# Pg4-Power_supply_1.net
KiCad netlist of a schematic drawn in Altium Designer
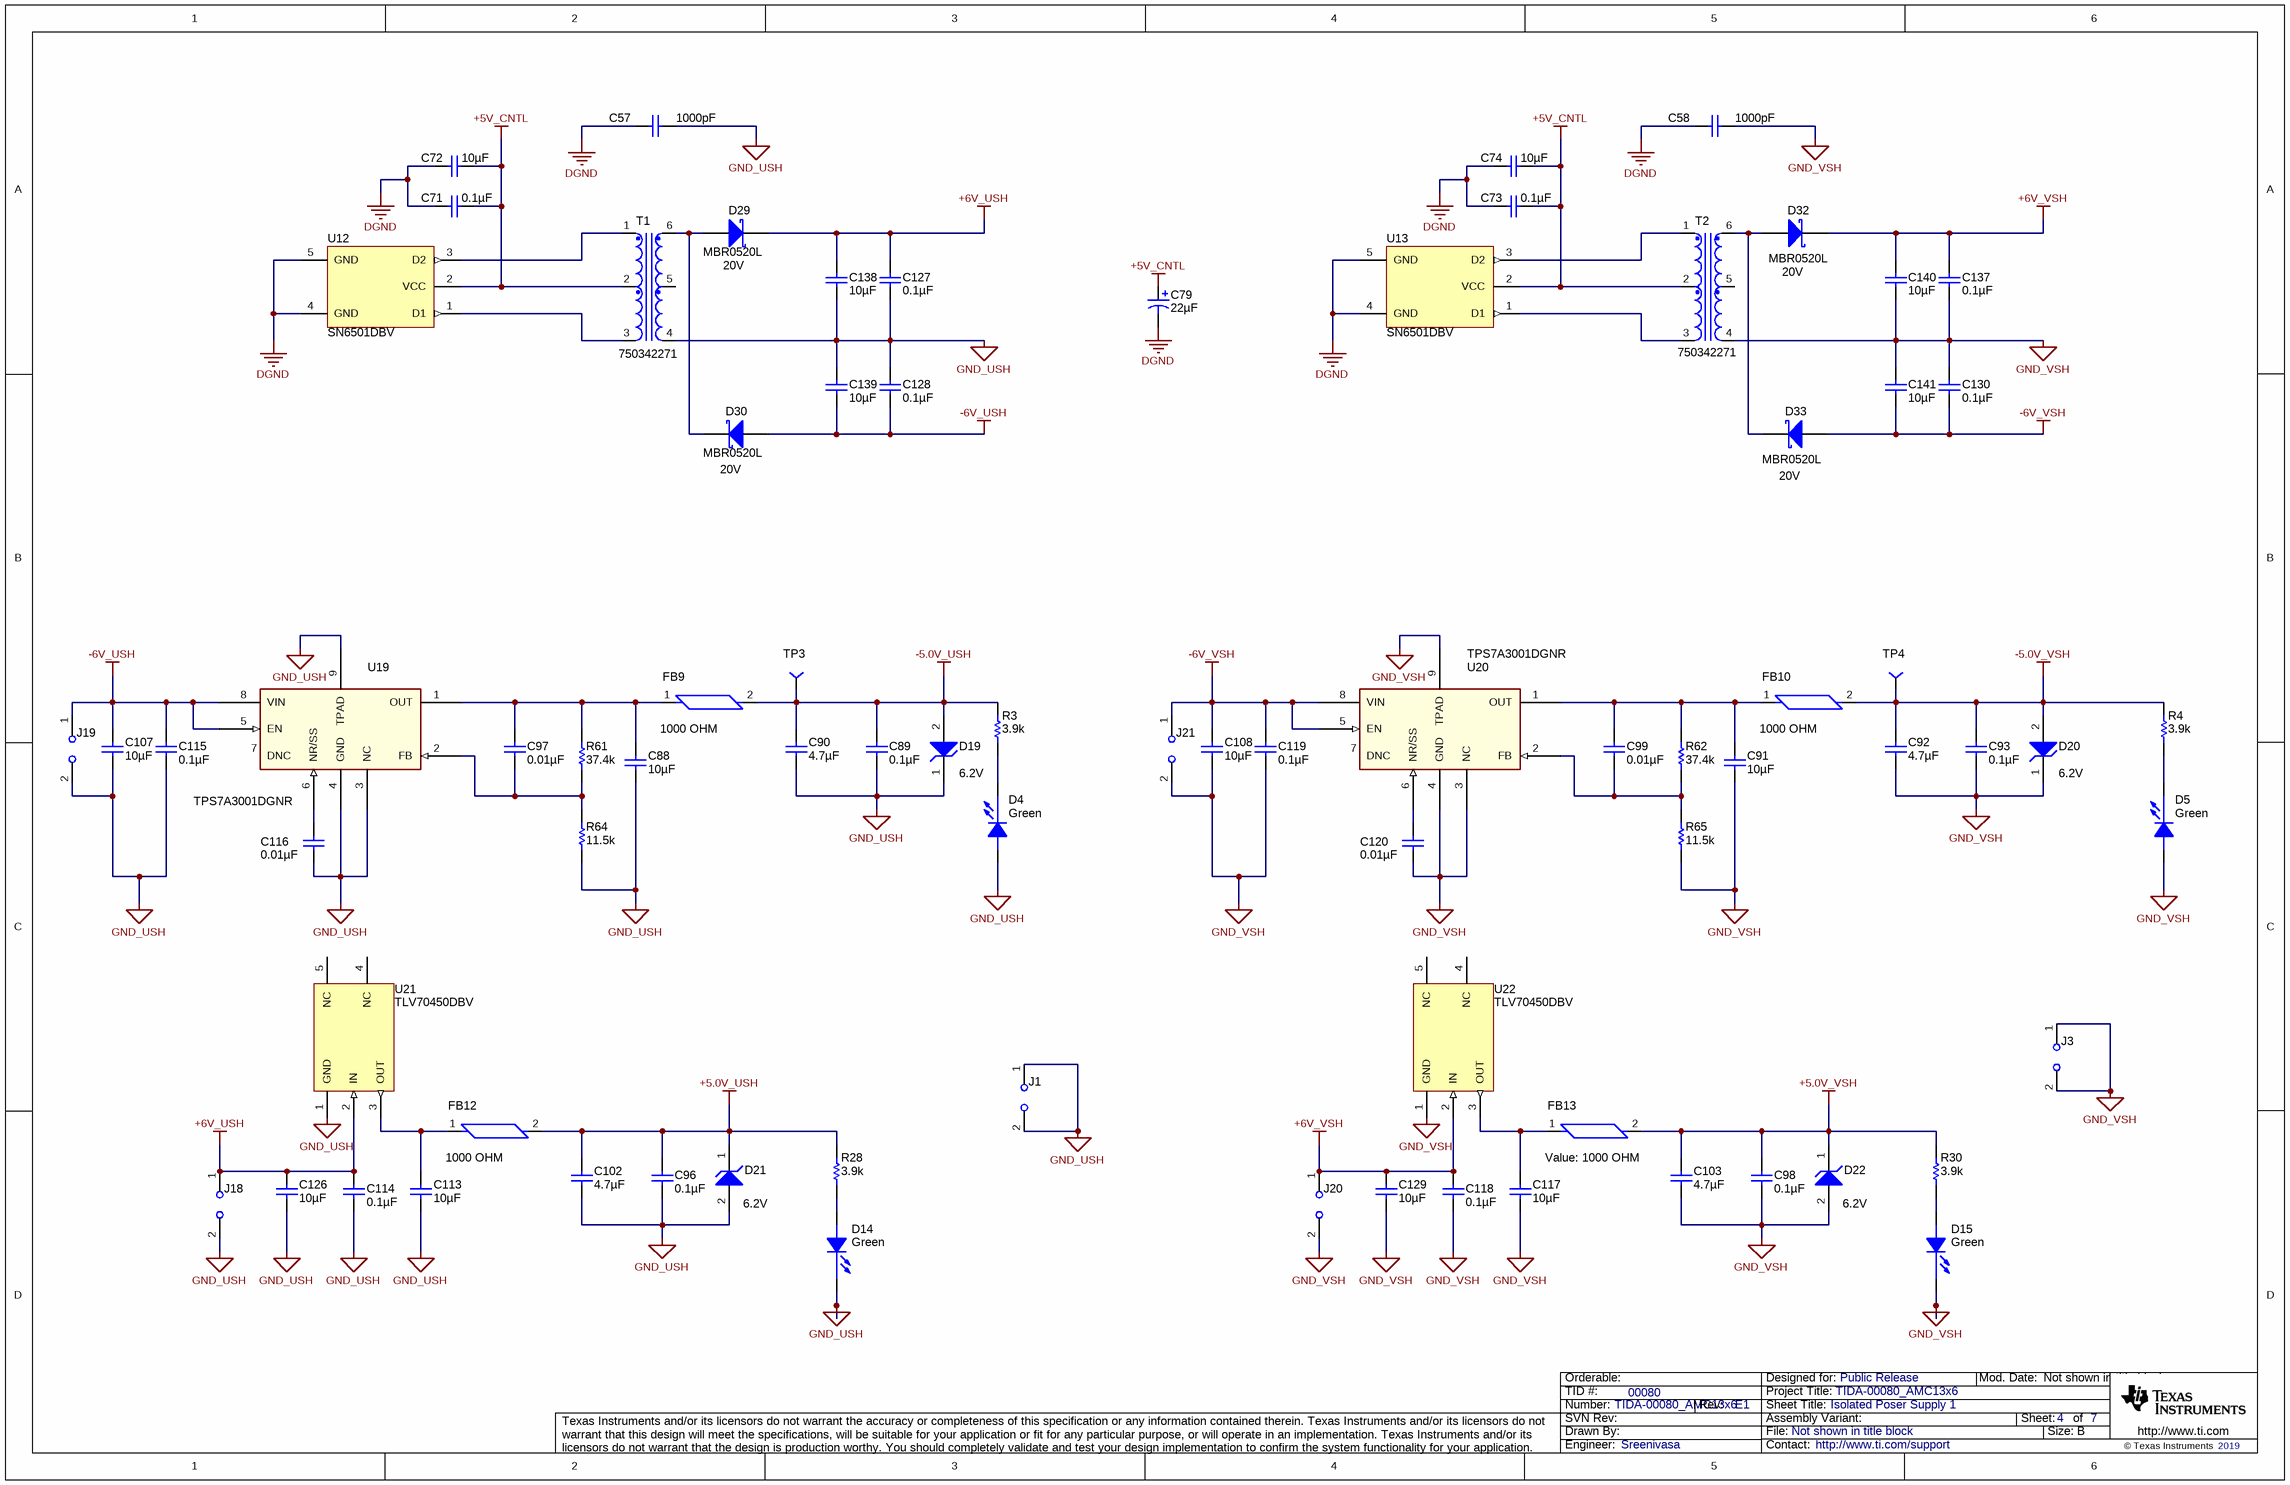
[diagram p0: Pg4-Power supply 1.SchDoc]

(export (version "E")
  (design (tool "Eeschema 10.0.6"))
  (components
    (comp (ref "C57")
      (value "1000pF")
      (footprint "CAP_200mil")
      (description "CAP CER 1000PF 1KV 10% RADIAL")
      (fields
        (field (name "PARTNUMBER") "S102K29Y5PN63J5R")
        (field (name "MANUFACTURER") "Vishay BC Components")
        (field (name "PUBLISHER") "Texas Instruments")
      )
      (libsource (lib "TI-INDIA-ALTIUM") (part "202R18W102KV4E"))
    )
    (comp (ref "C58")
      (value "1000pF")
      (footprint "CAP_200mil")
      (description "CAP CER 1000PF 1KV 10% RADIAL")
      (fields
        (field (name "PARTNUMBER") "S102K29Y5PN63J5R")
        (field (name "MANUFACTURER") "Vishay BC Components")
        (field (name "PUBLISHER") "Texas Instruments")
      )
      (libsource (lib "TI-INDIA-ALTIUM") (part "202R18W102KV4E"))
    )
    (comp (ref "C71")
      (value "~")
      (footprint "ISE_MCS_SDM_E1_20MAY:0603")
      (description "CAP, CERM, 0.1uF, 50V, +/-10%, X7R, 0603")
      (fields
        (field (name "PARTNUMBER") "C0603C104K5RACTU")
        (field (name "VALUEDISPLAYED") "0.1µF")
        (field (name "MANUFACTURER") "Kemet")
        (field (name "PUBLISHER") "Texas Instruments")
      )
      (libsource (lib "Capacitor_Ceramic") (part "C0603C104K5RACTU"))
    )
    (comp (ref "C72")
      (value "~")
      (footprint "ISE_MCS_SDM_E1_20MAY:1210")
      (description "CAP, CERM, 10uF, 35V, +/-20%, X7R, 1210")
      (fields
        (field (name "PARTNUMBER") "GMK325AB7106MM-T")
        (field (name "VALUEDISPLAYED") "10µF")
        (field (name "MANUFACTURER") "Taiyo Yuden")
        (field (name "PUBLISHER") "Texas Instruments")
      )
      (libsource (lib "Capacitor_Ceramic") (part "GMK325AB7106MM-T"))
    )
    (comp (ref "C73")
      (value "~")
      (footprint "ISE_MCS_SDM_E1_20MAY:0603")
      (description "CAP, CERM, 0.1uF, 50V, +/-10%, X7R, 0603")
      (fields
        (field (name "PARTNUMBER") "C0603C104K5RACTU")
        (field (name "VALUEDISPLAYED") "0.1µF")
        (field (name "MANUFACTURER") "Kemet")
        (field (name "PUBLISHER") "Texas Instruments")
      )
      (libsource (lib "Capacitor_Ceramic") (part "C0603C104K5RACTU"))
    )
    (comp (ref "C74")
      (value "~")
      (footprint "ISE_MCS_SDM_E1_20MAY:1210")
      (description "CAP, CERM, 10uF, 35V, +/-20%, X7R, 1210")
      (fields
        (field (name "PARTNUMBER") "GMK325AB7106MM-T")
        (field (name "VALUEDISPLAYED") "10µF")
        (field (name "MANUFACTURER") "Taiyo Yuden")
        (field (name "PUBLISHER") "Texas Instruments")
      )
      (libsource (lib "Capacitor_Ceramic") (part "GMK325AB7106MM-T"))
    )
    (comp (ref "C79")
      (value "UUD1E220MCL1GS")
      (footprint "ISE_MCS_SDM_E1_20MAY:SM_RADIAL_5MM")
      (description "CAP, AL, 22uF, 25V, +/-20%, 0.76 ohm, SMD")
      (fields
        (field (name "VALUEDISPLAYED") "22µF")
        (field (name "MANUFACTURER") "Nichicon")
        (field (name "PUBLISHER") "Texas Instruments")
      )
      (libsource (lib "Capacitor_Aluminum") (part "UUD1E220MCL1GS"))
    )
    (comp (ref "C88")
      (value "~")
      (footprint "ISE_MCS_SDM_E1_20MAY:1210")
      (description "CAP, CERM, 10uF, 35V, +/-20%, X7R, 1210")
      (fields
        (field (name "PARTNUMBER") "GMK325AB7106MM-T")
        (field (name "VALUEDISPLAYED") "10µF")
        (field (name "MANUFACTURER") "Taiyo Yuden")
        (field (name "PUBLISHER") "Texas Instruments")
      )
      (libsource (lib "Capacitor_Ceramic") (part "GMK325AB7106MM-T"))
    )
    (comp (ref "C89")
      (value "~")
      (footprint "ISE_MCS_SDM_E1_20MAY:0603")
      (description "CAP, CERM, 0.1uF, 50V, +/-10%, X7R, 0603")
      (fields
        (field (name "PARTNUMBER") "C0603C104K5RACTU")
        (field (name "VALUEDISPLAYED") "0.1µF")
        (field (name "MANUFACTURER") "Kemet")
        (field (name "PUBLISHER") "Texas Instruments")
      )
      (libsource (lib "Capacitor_Ceramic") (part "C0603C104K5RACTU"))
    )
    (comp (ref "C90")
      (value "~")
      (footprint "ISE_MCS_SDM_E1_20MAY:0805_HV")
      (description "CAP, CERM, 4.7uF, 50V, +/-10%, X5R, 0805")
      (fields
        (field (name "PARTNUMBER") "C2012X5R1H475K125AB")
        (field (name "VALUEDISPLAYED") "4.7µF")
        (field (name "MANUFACTURER") "TDK")
        (field (name "PUBLISHER") "Texas Instruments")
      )
      (libsource (lib "Capacitor_Ceramic") (part "C2012X5R1H475K125AB"))
    )
    (comp (ref "C91")
      (value "~")
      (footprint "ISE_MCS_SDM_E1_20MAY:1210")
      (description "CAP, CERM, 10uF, 35V, +/-20%, X7R, 1210")
      (fields
        (field (name "PARTNUMBER") "GMK325AB7106MM-T")
        (field (name "VALUEDISPLAYED") "10µF")
        (field (name "MANUFACTURER") "Taiyo Yuden")
        (field (name "PUBLISHER") "Texas Instruments")
      )
      (libsource (lib "Capacitor_Ceramic") (part "GMK325AB7106MM-T"))
    )
    (comp (ref "C92")
      (value "~")
      (footprint "ISE_MCS_SDM_E1_20MAY:0805_HV")
      (description "CAP, CERM, 4.7uF, 50V, +/-10%, X5R, 0805")
      (fields
        (field (name "PARTNUMBER") "C2012X5R1H475K125AB")
        (field (name "VALUEDISPLAYED") "4.7µF")
        (field (name "MANUFACTURER") "TDK")
        (field (name "PUBLISHER") "Texas Instruments")
      )
      (libsource (lib "Capacitor_Ceramic") (part "C2012X5R1H475K125AB"))
    )
    (comp (ref "C93")
      (value "~")
      (footprint "ISE_MCS_SDM_E1_20MAY:0603")
      (description "CAP, CERM, 0.1uF, 50V, +/-10%, X7R, 0603")
      (fields
        (field (name "PARTNUMBER") "C0603C104K5RACTU")
        (field (name "VALUEDISPLAYED") "0.1µF")
        (field (name "MANUFACTURER") "Kemet")
        (field (name "PUBLISHER") "Texas Instruments")
      )
      (libsource (lib "Capacitor_Ceramic") (part "C0603C104K5RACTU"))
    )
    (comp (ref "C96")
      (value "~")
      (footprint "ISE_MCS_SDM_E1_20MAY:0603")
      (description "CAP, CERM, 0.1uF, 50V, +/-10%, X7R, 0603")
      (fields
        (field (name "PARTNUMBER") "C0603C104K5RACTU")
        (field (name "VALUEDISPLAYED") "0.1µF")
        (field (name "MANUFACTURER") "Kemet")
        (field (name "PUBLISHER") "Texas Instruments")
      )
      (libsource (lib "Capacitor_Ceramic") (part "C0603C104K5RACTU"))
    )
    (comp (ref "C97")
      (value "~")
      (footprint "ISE_MCS_SDM_E1_20MAY:0603")
      (description "CAP, CERM, 0.01uF, 100V, +/-5%, X7R, 0603")
      (fields
        (field (name "PARTNUMBER") "06031C103J4Z4A")
        (field (name "VALUEDISPLAYED") "0.01µF")
        (field (name "MANUFACTURER") "AVX")
        (field (name "PUBLISHER") "Texas Instruments")
      )
      (libsource (lib "Capacitor_Ceramic") (part "06031C103JAT2A"))
    )
    (comp (ref "C98")
      (value "~")
      (footprint "ISE_MCS_SDM_E1_20MAY:0603")
      (description "CAP, CERM, 0.1uF, 50V, +/-10%, X7R, 0603")
      (fields
        (field (name "PARTNUMBER") "C0603C104K5RACTU")
        (field (name "VALUEDISPLAYED") "0.1µF")
        (field (name "MANUFACTURER") "Kemet")
        (field (name "PUBLISHER") "Texas Instruments")
      )
      (libsource (lib "Capacitor_Ceramic") (part "C0603C104K5RACTU"))
    )
    (comp (ref "C99")
      (value "~")
      (footprint "ISE_MCS_SDM_E1_20MAY:0603")
      (description "CAP, CERM, 0.01uF, 100V, +/-5%, X7R, 0603")
      (fields
        (field (name "PARTNUMBER") "06031C103J4Z4A")
        (field (name "VALUEDISPLAYED") "0.01µF")
        (field (name "MANUFACTURER") "AVX")
        (field (name "PUBLISHER") "Texas Instruments")
      )
      (libsource (lib "Capacitor_Ceramic") (part "06031C103JAT2A"))
    )
    (comp (ref "C102")
      (value "~")
      (footprint "ISE_MCS_SDM_E1_20MAY:0805_HV")
      (description "CAP, CERM, 4.7uF, 50V, +/-10%, X5R, 0805")
      (fields
        (field (name "PARTNUMBER") "C2012X5R1H475K125AB")
        (field (name "VALUEDISPLAYED") "4.7µF")
        (field (name "MANUFACTURER") "TDK")
        (field (name "PUBLISHER") "Texas Instruments")
      )
      (libsource (lib "Capacitor_Ceramic") (part "C2012X5R1H475K125AB"))
    )
    (comp (ref "C103")
      (value "~")
      (footprint "ISE_MCS_SDM_E1_20MAY:0805_HV")
      (description "CAP, CERM, 4.7uF, 50V, +/-10%, X5R, 0805")
      (fields
        (field (name "PARTNUMBER") "C2012X5R1H475K125AB")
        (field (name "VALUEDISPLAYED") "4.7µF")
        (field (name "MANUFACTURER") "TDK")
        (field (name "PUBLISHER") "Texas Instruments")
      )
      (libsource (lib "Capacitor_Ceramic") (part "C2012X5R1H475K125AB"))
    )
    (comp (ref "C107")
      (value "~")
      (footprint "ISE_MCS_SDM_E1_20MAY:1210")
      (description "CAP, CERM, 10uF, 35V, +/-20%, X7R, 1210")
      (fields
        (field (name "PARTNUMBER") "GMK325AB7106MM-T")
        (field (name "VALUEDISPLAYED") "10µF")
        (field (name "MANUFACTURER") "Taiyo Yuden")
        (field (name "PUBLISHER") "Texas Instruments")
      )
      (libsource (lib "Capacitor_Ceramic") (part "GMK325AB7106MM-T"))
    )
    (comp (ref "C108")
      (value "~")
      (footprint "ISE_MCS_SDM_E1_20MAY:1210")
      (description "CAP, CERM, 10uF, 35V, +/-20%, X7R, 1210")
      (fields
        (field (name "PARTNUMBER") "GMK325AB7106MM-T")
        (field (name "VALUEDISPLAYED") "10µF")
        (field (name "MANUFACTURER") "Taiyo Yuden")
        (field (name "PUBLISHER") "Texas Instruments")
      )
      (libsource (lib "Capacitor_Ceramic") (part "GMK325AB7106MM-T"))
    )
    (comp (ref "C113")
      (value "~")
      (footprint "ISE_MCS_SDM_E1_20MAY:1210")
      (description "CAP, CERM, 10uF, 35V, +/-20%, X7R, 1210")
      (fields
        (field (name "PARTNUMBER") "GMK325AB7106MM-T")
        (field (name "VALUEDISPLAYED") "10µF")
        (field (name "MANUFACTURER") "Taiyo Yuden")
        (field (name "PUBLISHER") "Texas Instruments")
      )
      (libsource (lib "Capacitor_Ceramic") (part "GMK325AB7106MM-T"))
    )
    (comp (ref "C114")
      (value "~")
      (footprint "ISE_MCS_SDM_E1_20MAY:0603")
      (description "CAP, CERM, 0.1uF, 50V, +/-10%, X7R, 0603")
      (fields
        (field (name "PARTNUMBER") "C0603C104K5RACTU")
        (field (name "VALUEDISPLAYED") "0.1µF")
        (field (name "MANUFACTURER") "Kemet")
        (field (name "PUBLISHER") "Texas Instruments")
      )
      (libsource (lib "Capacitor_Ceramic") (part "C0603C104K5RACTU"))
    )
    (comp (ref "C115")
      (value "~")
      (footprint "ISE_MCS_SDM_E1_20MAY:0603")
      (description "CAP, CERM, 0.1uF, 50V, +/-10%, X7R, 0603")
      (fields
        (field (name "PARTNUMBER") "C0603C104K5RACTU")
        (field (name "VALUEDISPLAYED") "0.1µF")
        (field (name "MANUFACTURER") "Kemet")
        (field (name "PUBLISHER") "Texas Instruments")
      )
      (libsource (lib "Capacitor_Ceramic") (part "C0603C104K5RACTU"))
    )
    (comp (ref "C116")
      (value "~")
      (footprint "ISE_MCS_SDM_E1_20MAY:0603")
      (description "CAP, CERM, 0.01uF, 100V, +/-5%, X7R, 0603")
      (fields
        (field (name "PARTNUMBER") "06031C103J4Z4A")
        (field (name "VALUEDISPLAYED") "0.01µF")
        (field (name "MANUFACTURER") "AVX")
        (field (name "PUBLISHER") "Texas Instruments")
      )
      (libsource (lib "Capacitor_Ceramic") (part "06031C103JAT2A"))
    )
    (comp (ref "C117")
      (value "~")
      (footprint "ISE_MCS_SDM_E1_20MAY:1210")
      (description "CAP, CERM, 10uF, 35V, +/-20%, X7R, 1210")
      (fields
        (field (name "PARTNUMBER") "GMK325AB7106MM-T")
        (field (name "VALUEDISPLAYED") "10µF")
        (field (name "MANUFACTURER") "Taiyo Yuden")
        (field (name "PUBLISHER") "Texas Instruments")
      )
      (libsource (lib "Capacitor_Ceramic") (part "GMK325AB7106MM-T"))
    )
    (comp (ref "C118")
      (value "~")
      (footprint "ISE_MCS_SDM_E1_20MAY:0603")
      (description "CAP, CERM, 0.1uF, 50V, +/-10%, X7R, 0603")
      (fields
        (field (name "PARTNUMBER") "C0603C104K5RACTU")
        (field (name "VALUEDISPLAYED") "0.1µF")
        (field (name "MANUFACTURER") "Kemet")
        (field (name "PUBLISHER") "Texas Instruments")
      )
      (libsource (lib "Capacitor_Ceramic") (part "C0603C104K5RACTU"))
    )
    (comp (ref "C119")
      (value "~")
      (footprint "ISE_MCS_SDM_E1_20MAY:0603")
      (description "CAP, CERM, 0.1uF, 50V, +/-10%, X7R, 0603")
      (fields
        (field (name "PARTNUMBER") "C0603C104K5RACTU")
        (field (name "VALUEDISPLAYED") "0.1µF")
        (field (name "MANUFACTURER") "Kemet")
        (field (name "PUBLISHER") "Texas Instruments")
      )
      (libsource (lib "Capacitor_Ceramic") (part "C0603C104K5RACTU"))
    )
    (comp (ref "C120")
      (value "~")
      (footprint "ISE_MCS_SDM_E1_20MAY:0603")
      (description "CAP, CERM, 0.01uF, 100V, +/-5%, X7R, 0603")
      (fields
        (field (name "PARTNUMBER") "06031C103J4Z4A")
        (field (name "VALUEDISPLAYED") "0.01µF")
        (field (name "MANUFACTURER") "AVX")
        (field (name "PUBLISHER") "Texas Instruments")
      )
      (libsource (lib "Capacitor_Ceramic") (part "06031C103JAT2A"))
    )
    (comp (ref "C126")
      (value "~")
      (footprint "ISE_MCS_SDM_E1_20MAY:1210")
      (description "CAP, CERM, 10uF, 35V, +/-20%, X7R, 1210")
      (fields
        (field (name "PARTNUMBER") "GMK325AB7106MM-T")
        (field (name "VALUEDISPLAYED") "10µF")
        (field (name "MANUFACTURER") "Taiyo Yuden")
        (field (name "PUBLISHER") "Texas Instruments")
      )
      (libsource (lib "Capacitor_Ceramic") (part "GMK325AB7106MM-T"))
    )
    (comp (ref "C127")
      (value "~")
      (footprint "ISE_MCS_SDM_E1_20MAY:0603")
      (description "CAP, CERM, 0.1uF, 50V, +/-10%, X7R, 0603")
      (fields
        (field (name "PARTNUMBER") "C0603C104K5RACTU")
        (field (name "VALUEDISPLAYED") "0.1µF")
        (field (name "MANUFACTURER") "Kemet")
        (field (name "PUBLISHER") "Texas Instruments")
      )
      (libsource (lib "Capacitor_Ceramic") (part "C0603C104K5RACTU"))
    )
    (comp (ref "C128")
      (value "~")
      (footprint "ISE_MCS_SDM_E1_20MAY:0603")
      (description "CAP, CERM, 0.1uF, 50V, +/-10%, X7R, 0603")
      (fields
        (field (name "PARTNUMBER") "C0603C104K5RACTU")
        (field (name "VALUEDISPLAYED") "0.1µF")
        (field (name "MANUFACTURER") "Kemet")
        (field (name "PUBLISHER") "Texas Instruments")
      )
      (libsource (lib "Capacitor_Ceramic") (part "C0603C104K5RACTU"))
    )
    (comp (ref "C129")
      (value "~")
      (footprint "ISE_MCS_SDM_E1_20MAY:1210")
      (description "CAP, CERM, 10uF, 35V, +/-20%, X7R, 1210")
      (fields
        (field (name "PARTNUMBER") "GMK325AB7106MM-T")
        (field (name "VALUEDISPLAYED") "10µF")
        (field (name "MANUFACTURER") "Taiyo Yuden")
        (field (name "PUBLISHER") "Texas Instruments")
      )
      (libsource (lib "Capacitor_Ceramic") (part "GMK325AB7106MM-T"))
    )
    (comp (ref "C130")
      (value "~")
      (footprint "ISE_MCS_SDM_E1_20MAY:0603")
      (description "CAP, CERM, 0.1uF, 50V, +/-10%, X7R, 0603")
      (fields
        (field (name "PARTNUMBER") "C0603C104K5RACTU")
        (field (name "VALUEDISPLAYED") "0.1µF")
        (field (name "MANUFACTURER") "Kemet")
        (field (name "PUBLISHER") "Texas Instruments")
      )
      (libsource (lib "Capacitor_Ceramic") (part "C0603C104K5RACTU"))
    )
    (comp (ref "C137")
      (value "~")
      (footprint "ISE_MCS_SDM_E1_20MAY:0603")
      (description "CAP, CERM, 0.1uF, 50V, +/-10%, X7R, 0603")
      (fields
        (field (name "PARTNUMBER") "C0603C104K5RACTU")
        (field (name "VALUEDISPLAYED") "0.1µF")
        (field (name "MANUFACTURER") "Kemet")
        (field (name "PUBLISHER") "Texas Instruments")
      )
      (libsource (lib "Capacitor_Ceramic") (part "C0603C104K5RACTU"))
    )
    (comp (ref "C138")
      (value "~")
      (footprint "ISE_MCS_SDM_E1_20MAY:1210")
      (description "CAP, CERM, 10uF, 35V, +/-20%, X7R, 1210")
      (fields
        (field (name "PARTNUMBER") "GMK325AB7106MM-T")
        (field (name "VALUEDISPLAYED") "10µF")
        (field (name "MANUFACTURER") "Taiyo Yuden")
        (field (name "PUBLISHER") "Texas Instruments")
      )
      (libsource (lib "Capacitor_Ceramic") (part "GMK325AB7106MM-T"))
    )
    (comp (ref "C139")
      (value "~")
      (footprint "ISE_MCS_SDM_E1_20MAY:1210")
      (description "CAP, CERM, 10uF, 35V, +/-20%, X7R, 1210")
      (fields
        (field (name "PARTNUMBER") "GMK325AB7106MM-T")
        (field (name "VALUEDISPLAYED") "10µF")
        (field (name "MANUFACTURER") "Taiyo Yuden")
        (field (name "PUBLISHER") "Texas Instruments")
      )
      (libsource (lib "Capacitor_Ceramic") (part "GMK325AB7106MM-T"))
    )
    (comp (ref "C140")
      (value "~")
      (footprint "ISE_MCS_SDM_E1_20MAY:1210")
      (description "CAP, CERM, 10uF, 35V, +/-20%, X7R, 1210")
      (fields
        (field (name "PARTNUMBER") "GMK325AB7106MM-T")
        (field (name "VALUEDISPLAYED") "10µF")
        (field (name "MANUFACTURER") "Taiyo Yuden")
        (field (name "PUBLISHER") "Texas Instruments")
      )
      (libsource (lib "Capacitor_Ceramic") (part "GMK325AB7106MM-T"))
    )
    (comp (ref "C141")
      (value "~")
      (footprint "ISE_MCS_SDM_E1_20MAY:1210")
      (description "CAP, CERM, 10uF, 35V, +/-20%, X7R, 1210")
      (fields
        (field (name "PARTNUMBER") "GMK325AB7106MM-T")
        (field (name "VALUEDISPLAYED") "10µF")
        (field (name "MANUFACTURER") "Taiyo Yuden")
        (field (name "PUBLISHER") "Texas Instruments")
      )
      (libsource (lib "Capacitor_Ceramic") (part "GMK325AB7106MM-T"))
    )
    (comp (ref "D4")
      (value "Green")
      (footprint "ISE_MCS_SDM_E1_20MAY:LED0603AA")
      (description "LED SmartLED Green 570NM")
      (fields
        (field (name "PARTNUMBER") "LG L29K-G2J1-24-Z")
        (field (name "MANUFACTURER") "OSRAM")
        (field (name "PUBLISHER") "TI")
        (field (name "SYMBOLCREATOR") "x0120606")
      )
      (libsource (lib "TI-INDIA-ALTIUM") (part "LED_LG L29K-G2J1-24-Z"))
    )
    (comp (ref "D5")
      (value "Green")
      (footprint "ISE_MCS_SDM_E1_20MAY:LED0603AA")
      (description "LED SmartLED Green 570NM")
      (fields
        (field (name "PARTNUMBER") "LG L29K-G2J1-24-Z")
        (field (name "MANUFACTURER") "OSRAM")
        (field (name "PUBLISHER") "TI")
        (field (name "SYMBOLCREATOR") "x0120606")
      )
      (libsource (lib "TI-INDIA-ALTIUM") (part "LED_LG L29K-G2J1-24-Z"))
    )
    (comp (ref "D14")
      (value "Green")
      (footprint "ISE_MCS_SDM_E1_20MAY:LED0603AA")
      (description "LED SmartLED Green 570NM")
      (fields
        (field (name "PARTNUMBER") "LG L29K-G2J1-24-Z")
        (field (name "MANUFACTURER") "OSRAM")
        (field (name "PUBLISHER") "TI")
        (field (name "SYMBOLCREATOR") "x0120606")
      )
      (libsource (lib "TI-INDIA-ALTIUM") (part "LED_LG L29K-G2J1-24-Z"))
    )
    (comp (ref "D15")
      (value "Green")
      (footprint "ISE_MCS_SDM_E1_20MAY:LED0603AA")
      (description "LED SmartLED Green 570NM")
      (fields
        (field (name "PARTNUMBER") "LG L29K-G2J1-24-Z")
        (field (name "MANUFACTURER") "OSRAM")
        (field (name "PUBLISHER") "TI")
        (field (name "SYMBOLCREATOR") "x0120606")
      )
      (libsource (lib "TI-INDIA-ALTIUM") (part "LED_LG L29K-G2J1-24-Z"))
    )
    (comp (ref "D19")
      (value "6.2V")
      (footprint "ISE_MCS_SDM_E1_20MAY:powerDI123")
      (description "Diode, Zener, 6.2V, 1W, PowerDI123")
      (fields
        (field (name "PARTNUMBER") "DFLZ6V2-7")
        (field (name "MANUFACTURER") "Diodes Inc.")
        (field (name "PUBLISHER") "Texas Instruments")
      )
      (libsource (lib "ZenerDiodes") (part "DFLZ6V2-7"))
    )
    (comp (ref "D20")
      (value "6.2V")
      (footprint "ISE_MCS_SDM_E1_20MAY:powerDI123")
      (description "Diode, Zener, 6.2V, 1W, PowerDI123")
      (fields
        (field (name "PARTNUMBER") "DFLZ6V2-7")
        (field (name "MANUFACTURER") "Diodes Inc.")
        (field (name "PUBLISHER") "Texas Instruments")
      )
      (libsource (lib "ZenerDiodes") (part "DFLZ6V2-7"))
    )
    (comp (ref "D21")
      (value "6.2V")
      (footprint "ISE_MCS_SDM_E1_20MAY:powerDI123")
      (description "Diode, Zener, 6.2V, 1W, PowerDI123")
      (fields
        (field (name "PARTNUMBER") "DFLZ6V2-7")
        (field (name "MANUFACTURER") "Diodes Inc.")
        (field (name "PUBLISHER") "Texas Instruments")
      )
      (libsource (lib "ZenerDiodes") (part "DFLZ6V2-7"))
    )
    (comp (ref "D22")
      (value "6.2V")
      (footprint "ISE_MCS_SDM_E1_20MAY:powerDI123")
      (description "Diode, Zener, 6.2V, 1W, PowerDI123")
      (fields
        (field (name "PARTNUMBER") "DFLZ6V2-7")
        (field (name "MANUFACTURER") "Diodes Inc.")
        (field (name "PUBLISHER") "Texas Instruments")
      )
      (libsource (lib "ZenerDiodes") (part "DFLZ6V2-7"))
    )
    (comp (ref "D29")
      (value "MBR0520L")
      (footprint "ISE_MCS_SDM_E1_20MAY:SOD-123")
      (description "Diode, Schottky, 20V, 0.5A, SOD-123")
      (fields
        (field (name "ALTIUM_VALUE") "20V")
        (field (name "MANUFACTURER") "Fairchild Semiconductor")
        (field (name "PUBLISHER") "Texas Instruments")
      )
      (libsource (lib "Diode") (part "MBR0520LT1G"))
    )
    (comp (ref "D30")
      (value "MBR0520L")
      (footprint "ISE_MCS_SDM_E1_20MAY:SOD-123")
      (description "Diode, Schottky, 20V, 0.5A, SOD-123")
      (fields
        (field (name "ALTIUM_VALUE") "20V")
        (field (name "MANUFACTURER") "Fairchild Semiconductor")
        (field (name "PUBLISHER") "Texas Instruments")
      )
      (libsource (lib "Diode") (part "MBR0520LT1G"))
    )
    (comp (ref "D32")
      (value "MBR0520L")
      (footprint "ISE_MCS_SDM_E1_20MAY:SOD-123")
      (description "Diode, Schottky, 20V, 0.5A, SOD-123")
      (fields
        (field (name "ALTIUM_VALUE") "20V")
        (field (name "MANUFACTURER") "Fairchild Semiconductor")
        (field (name "PUBLISHER") "Texas Instruments")
      )
      (libsource (lib "Diode") (part "MBR0520LT1G"))
    )
    (comp (ref "D33")
      (value "MBR0520L")
      (footprint "ISE_MCS_SDM_E1_20MAY:SOD-123")
      (description "Diode, Schottky, 20V, 0.5A, SOD-123")
      (fields
        (field (name "ALTIUM_VALUE") "20V")
        (field (name "MANUFACTURER") "Fairchild Semiconductor")
        (field (name "PUBLISHER") "Texas Instruments")
      )
      (libsource (lib "Diode") (part "MBR0520LT1G"))
    )
    (comp (ref "FB9")
      (value "1000 OHM")
      (footprint "ISE_MCS_SDM_E1_20MAY:FB0603")
      (description "FERRITE CHIP 1000 OHM 300MA 0603")
      (fields
        (field (name "PARTNUMBER") "MMZ1608B102C")
        (field (name "MANUFACTURER") "TDK Corporation")
        (field (name "PUBLISHER") "TI")
      )
      (libsource (lib "TI-INDIA-ALTIUM") (part "MMZ1608B102C"))
    )
    (comp (ref "FB10")
      (value "1000 OHM")
      (footprint "ISE_MCS_SDM_E1_20MAY:FB0603")
      (description "FERRITE CHIP 1000 OHM 300MA 0603")
      (fields
        (field (name "PARTNUMBER") "MMZ1608B102C")
        (field (name "MANUFACTURER") "TDK Corporation")
        (field (name "PUBLISHER") "TI")
      )
      (libsource (lib "TI-INDIA-ALTIUM") (part "MMZ1608B102C"))
    )
    (comp (ref "FB12")
      (value "1000 OHM")
      (footprint "ISE_MCS_SDM_E1_20MAY:FB0603")
      (description "FERRITE CHIP 1000 OHM 300MA 0603")
      (fields
        (field (name "PARTNUMBER") "MMZ1608B102C")
        (field (name "MANUFACTURER") "TDK Corporation")
        (field (name "PUBLISHER") "TI")
      )
      (libsource (lib "TI-INDIA-ALTIUM") (part "MMZ1608B102C"))
    )
    (comp (ref "FB13")
      (value "1000 OHM")
      (footprint "ISE_MCS_SDM_E1_20MAY:FB0603")
      (description "FERRITE CHIP 1000 OHM 300MA 0603")
      (fields
        (field (name "PARTNUMBER") "MMZ1608B102C")
        (field (name "MANUFACTURER") "TDK Corporation")
        (field (name "PUBLISHER") "TI")
      )
      (libsource (lib "TI-INDIA-ALTIUM") (part "MMZ1608B102C"))
    )
    (comp (ref "J1")
      (value "~")
      (footprint "ISE_MCS_SDM_E1_20MAY:HDR100_1X2")
      (description "Header, Male 2-pin, 100mil spacing,")
      (fields (field (name "MANUFACTURER") "FCI") (field (name "PARTNUMBER") "68001-402HLF"))
      (libsource (lib "PADSlegacy_Hardware") (part "JUMPER_2X100MIL"))
    )
    (comp (ref "J3")
      (value "~")
      (footprint "ISE_MCS_SDM_E1_20MAY:HDR100_1X2")
      (description "Header, Male 2-pin, 100mil spacing,")
      (fields (field (name "MANUFACTURER") "FCI") (field (name "PARTNUMBER") "68001-402HLF"))
      (libsource (lib "PADSlegacy_Hardware") (part "JUMPER_2X100MIL"))
    )
    (comp (ref "J18")
      (value "~")
      (footprint "ISE_MCS_SDM_E1_20MAY:HDR100_1X2")
      (description "Header, Male 2-pin, 100mil spacing,")
      (fields (field (name "MANUFACTURER") "FCI") (field (name "PARTNUMBER") "68001-402HLF"))
      (libsource (lib "PADSlegacy_Hardware") (part "JUMPER_2X100MIL"))
    )
    (comp (ref "J19")
      (value "~")
      (footprint "ISE_MCS_SDM_E1_20MAY:HDR100_1X2")
      (description "Header, Male 2-pin, 100mil spacing,")
      (fields (field (name "MANUFACTURER") "FCI") (field (name "PARTNUMBER") "68001-402HLF"))
      (libsource (lib "PADSlegacy_Hardware") (part "JUMPER_2X100MIL"))
    )
    (comp (ref "J20")
      (value "~")
      (footprint "ISE_MCS_SDM_E1_20MAY:HDR100_1X2")
      (description "Header, Male 2-pin, 100mil spacing,")
      (fields (field (name "MANUFACTURER") "FCI") (field (name "PARTNUMBER") "68001-402HLF"))
      (libsource (lib "PADSlegacy_Hardware") (part "JUMPER_2X100MIL"))
    )
    (comp (ref "J21")
      (value "~")
      (footprint "ISE_MCS_SDM_E1_20MAY:HDR100_1X2")
      (description "Header, Male 2-pin, 100mil spacing,")
      (fields (field (name "MANUFACTURER") "FCI") (field (name "PARTNUMBER") "68001-402HLF"))
      (libsource (lib "PADSlegacy_Hardware") (part "JUMPER_2X100MIL"))
    )
    (comp (ref "R3")
      (value "3.9k")
      (footprint "ISE_MCS_SDM_E1_20MAY:0603")
      (description "RES, 3.9k ohm, 5%, 0.1W, 0603")
      (fields
        (field (name "PARTNUMBER") "CRCW06033K90JNEA")
        (field (name "MANUFACTURER") "Vishay-Dale")
        (field (name "PUBLISHER") "Texas Instruments")
      )
      (libsource (lib "Resistor_0603") (part "CRCW06033K90JNEA"))
    )
    (comp (ref "R4")
      (value "3.9k")
      (footprint "ISE_MCS_SDM_E1_20MAY:0603")
      (description "RES, 3.9k ohm, 5%, 0.1W, 0603")
      (fields
        (field (name "PARTNUMBER") "CRCW06033K90JNEA")
        (field (name "MANUFACTURER") "Vishay-Dale")
        (field (name "PUBLISHER") "Texas Instruments")
      )
      (libsource (lib "Resistor_0603") (part "CRCW06033K90JNEA"))
    )
    (comp (ref "R28")
      (value "3.9k")
      (footprint "ISE_MCS_SDM_E1_20MAY:0603")
      (description "RES, 3.9k ohm, 5%, 0.1W, 0603")
      (fields
        (field (name "PARTNUMBER") "CRCW06033K90JNEA")
        (field (name "MANUFACTURER") "Vishay-Dale")
        (field (name "PUBLISHER") "Texas Instruments")
      )
      (libsource (lib "Resistor_0603") (part "CRCW06033K90JNEA"))
    )
    (comp (ref "R30")
      (value "3.9k")
      (footprint "ISE_MCS_SDM_E1_20MAY:0603")
      (description "RES, 3.9k ohm, 5%, 0.1W, 0603")
      (fields
        (field (name "PARTNUMBER") "CRCW06033K90JNEA")
        (field (name "MANUFACTURER") "Vishay-Dale")
        (field (name "PUBLISHER") "Texas Instruments")
      )
      (libsource (lib "Resistor_0603") (part "CRCW06033K90JNEA"))
    )
    (comp (ref "R61")
      (value "37.4k")
      (footprint "ISE_MCS_SDM_E1_20MAY:0603")
      (description "RES 37.4K OHM 1/10W .1% 0603 SMD")
      (fields
        (field (name "PARTNUMBER") "ERA-3AEB3742V")
        (field (name "MANUFACTURER") "Panasonic")
        (field (name "PUBLISHER") "Texas Instruments")
      )
      (libsource (lib "Resistor_0603") (part "RT0603BRD0737KL"))
    )
    (comp (ref "R62")
      (value "37.4k")
      (footprint "ISE_MCS_SDM_E1_20MAY:0603")
      (description "RES 37.4K OHM 1/10W .1% 0603 SMD")
      (fields
        (field (name "PARTNUMBER") "ERA-3AEB3742V")
        (field (name "MANUFACTURER") "Panasonic")
        (field (name "PUBLISHER") "Texas Instruments")
      )
      (libsource (lib "Resistor_0603") (part "RT0603BRD0737KL"))
    )
    (comp (ref "R64")
      (value "11.5k")
      (footprint "ISE_MCS_SDM_E1_20MAY:0603")
      (description "RES, 11.5k ohm, 1%, 0.1W, 0603")
      (fields
        (field (name "PARTNUMBER") "CRCW060311K5FKEA")
        (field (name "MANUFACTURER") "Vishay-Dale")
        (field (name "PUBLISHER") "Texas Instruments")
      )
      (libsource (lib "Resistor_0603") (part "CRCW060311K5FKEA"))
    )
    (comp (ref "R65")
      (value "11.5k")
      (footprint "ISE_MCS_SDM_E1_20MAY:0603")
      (description "RES, 11.5k ohm, 1%, 0.1W, 0603")
      (fields
        (field (name "PARTNUMBER") "CRCW060311K5FKEA")
        (field (name "MANUFACTURER") "Vishay-Dale")
        (field (name "PUBLISHER") "Texas Instruments")
      )
      (libsource (lib "Resistor_0603") (part "CRCW060311K5FKEA"))
    )
    (comp (ref "T1")
      (value "750342271")
      (footprint "760390015")
      (description "Transformer 469uH SMD")
      (fields (field (name "MANUFACTURER") "Wurth Electronics Midcom") (field (name "PUBLISHER") "TI"))
      (libsource (lib "Isolated current sensing") (part "TRNSFMR"))
    )
    (comp (ref "T2")
      (value "750342271")
      (footprint "760390015")
      (description "Transformer 469uH SMD")
      (fields (field (name "MANUFACTURER") "Wurth Electronics Midcom") (field (name "PUBLISHER") "TI"))
      (libsource (lib "Isolated current sensing") (part "TRNSFMR"))
    )
    (comp (ref "TP3")
      (value "~")
      (footprint "ISE_MCS_SDM_E1_20MAY:TP-040_RND")
      (description "Test Point, O.040 Hole")
      (fields (field (name "MANUFACTURER") "STD"))
      (libsource (lib "PADSlegacy_Hardware") (part "TP-040_RND"))
    )
    (comp (ref "TP4")
      (value "~")
      (footprint "ISE_MCS_SDM_E1_20MAY:TP-040_RND")
      (description "Test Point, O.040 Hole")
      (fields (field (name "MANUFACTURER") "STD"))
      (libsource (lib "PADSlegacy_Hardware") (part "TP-040_RND"))
    )
    (comp (ref "U12")
      (value "SN6501DBV")
      (footprint "ISE_MCS_SDM_E1_20MAY:DBV0005A_N")
      (description "Transformer Driver for Isolated Power Supplies, DBV0005A")
      (fields
        (field (name "MANUFACTURER") "Texas Instruments")
        (field (name "SYMBOLCREATOR") "a0411947")
        (field (name "PUBLISHER") "Texas Instruments")
      )
      (libsource (lib "TI_Pre_Release") (part "SN6501DBV"))
    )
    (comp (ref "U13")
      (value "SN6501DBV")
      (footprint "ISE_MCS_SDM_E1_20MAY:DBV0005A_N")
      (description "Transformer Driver for Isolated Power Supplies, DBV0005A")
      (fields
        (field (name "MANUFACTURER") "Texas Instruments")
        (field (name "SYMBOLCREATOR") "a0411947")
        (field (name "PUBLISHER") "Texas Instruments")
      )
      (libsource (lib "TI_Pre_Release") (part "SN6501DBV"))
    )
    (comp (ref "U19")
      (value "TPS7A3001DGNR")
      (footprint "ISE_MCS_SDM_E1_20MAY:MSOP8(DGN)")
      (description "-36V, -200mA, Ultralow-Noise, Negative Linear Regulator")
      (fields
        (field (name "MANUFACTURER") "Texas Instruments")
        (field (name "PUBLISHER") "Texas Instruments")
        (field (name "SYMBOLCREATOR") "x0120606")
      )
      (libsource (lib "TI-INDIA-ALTIUM") (part "TPS7A3001DGNR"))
    )
    (comp (ref "U20")
      (value "~")
      (footprint "ISE_MCS_SDM_E1_20MAY:MSOP8(DGN)")
      (description "-36V, -200mA, Ultralow-Noise, Negative Linear Regulator")
      (fields
        (field (name "MANUFACTURER") "Texas Instruments")
        (field (name "PARTNUMBER") "TPS7A3001DGNR")
        (field (name "PUBLISHER") "Texas Instruments")
        (field (name "SYMBOLCREATOR") "x0120606")
      )
      (libsource (lib "TI-INDIA-ALTIUM") (part "TPS7A3001DGNR"))
    )
    (comp (ref "U21")
      (value "TLV70450DBV")
      (footprint "ISE_MCS_SDM_E1_20MAY:DBV0005A_N")
      (description "Regulator, LDO, 5V, 0.15A, SOT23-5")
      (fields
        (field (name "MANUFACTURER") "Texas Instruments")
        (field (name "SYMBOLCREATOR") "x0120606")
        (field (name "PUBLISHER") "Texas Instruments")
      )
      (libsource (lib "TI-INDIA-ALTIUM") (part "TLV70450DBV"))
    )
    (comp (ref "U22")
      (value "TLV70450DBV")
      (footprint "ISE_MCS_SDM_E1_20MAY:DBV0005A_N")
      (description "Regulator, LDO, 5V, 0.15A, SOT23-5")
      (fields
        (field (name "MANUFACTURER") "Texas Instruments")
        (field (name "SYMBOLCREATOR") "x0120606")
        (field (name "PUBLISHER") "Texas Instruments")
      )
      (libsource (lib "TI-INDIA-ALTIUM") (part "TLV70450DBV"))
    )
  )
  (nets
    (net (code "1") (name "+5.0V_USH") (class "Default")
      (node (ref "C102") (pin "2") (pinfunction "2_2") (pintype "passive"))
      (node (ref "C96") (pin "1") (pinfunction "1_1") (pintype "passive"))
      (node (ref "D21") (pin "1") (pinfunction "K_1") (pintype "passive"))
      (node (ref "FB12") (pin "2") (pinfunction "2_2") (pintype "passive"))
      (node (ref "R28") (pin "2") (pinfunction "2_2") (pintype "passive"))
    )
    (net (code "2") (name "+5.0V_VSH") (class "Default")
      (node (ref "C103") (pin "2") (pinfunction "2_2") (pintype "passive"))
      (node (ref "C98") (pin "1") (pinfunction "1_1") (pintype "passive"))
      (node (ref "D22") (pin "1") (pinfunction "K_1") (pintype "passive"))
      (node (ref "FB13") (pin "2") (pinfunction "2_2") (pintype "passive"))
      (node (ref "R30") (pin "2") (pinfunction "2_2") (pintype "passive"))
    )
    (net (code "3") (name "+5V_CNTL") (class "Default")
      (node (ref "C71") (pin "2") (pinfunction "2_2") (pintype "passive"))
      (node (ref "C72") (pin "2") (pinfunction "2_2") (pintype "passive"))
      (node (ref "C73") (pin "2") (pinfunction "2_2") (pintype "passive"))
      (node (ref "C74") (pin "2") (pinfunction "2_2") (pintype "passive"))
      (node (ref "C79") (pin "1") (pinfunction "+_1") (pintype "passive"))
      (node (ref "T1") (pin "2") (pinfunction "2_2") (pintype "passive"))
      (node (ref "T2") (pin "2") (pinfunction "2_2") (pintype "passive"))
      (node (ref "U12") (pin "2") (pinfunction "VCC_2") (pintype "power_in"))
      (node (ref "U13") (pin "2") (pinfunction "VCC_2") (pintype "power_in"))
    )
    (net (code "4") (name "+6V_USH") (class "Default")
      (node (ref "C114") (pin "1") (pinfunction "1_1") (pintype "passive"))
      (node (ref "C126") (pin "2") (pinfunction "2_2") (pintype "passive"))
      (node (ref "C127") (pin "1") (pinfunction "1_1") (pintype "passive"))
      (node (ref "C138") (pin "1") (pinfunction "1_1") (pintype "passive"))
      (node (ref "D29") (pin "1") (pinfunction "K_1") (pintype "passive"))
      (node (ref "J18") (pin "1") (pintype "passive"))
      (node (ref "U21") (pin "2") (pinfunction "IN_2") (pintype "input"))
    )
    (net (code "5") (name "+6V_VSH") (class "Default")
      (node (ref "C118") (pin "1") (pinfunction "1_1") (pintype "passive"))
      (node (ref "C129") (pin "2") (pinfunction "2_2") (pintype "passive"))
      (node (ref "C137") (pin "1") (pinfunction "1_1") (pintype "passive"))
      (node (ref "C140") (pin "1") (pinfunction "1_1") (pintype "passive"))
      (node (ref "D32") (pin "1") (pinfunction "K_1") (pintype "passive"))
      (node (ref "J20") (pin "1") (pintype "passive"))
      (node (ref "U22") (pin "2") (pinfunction "IN_2") (pintype "input"))
    )
    (net (code "6") (name "-5.0V_USH") (class "Default")
      (node (ref "C89") (pin "1") (pinfunction "1_1") (pintype "passive"))
      (node (ref "C90") (pin "2") (pinfunction "2_2") (pintype "passive"))
      (node (ref "D19") (pin "2") (pinfunction "A_2") (pintype "passive"))
      (node (ref "FB9") (pin "2") (pinfunction "2_2") (pintype "passive"))
      (node (ref "R3") (pin "2") (pinfunction "2_2") (pintype "passive"))
      (node (ref "TP3") (pin "1") (pinfunction "1_1") (pintype "passive"))
    )
    (net (code "7") (name "-5.0V_VSH") (class "Default")
      (node (ref "C92") (pin "2") (pinfunction "2_2") (pintype "passive"))
      (node (ref "C93") (pin "1") (pinfunction "1_1") (pintype "passive"))
      (node (ref "D20") (pin "2") (pinfunction "A_2") (pintype "passive"))
      (node (ref "FB10") (pin "2") (pinfunction "2_2") (pintype "passive"))
      (node (ref "R4") (pin "2") (pinfunction "2_2") (pintype "passive"))
      (node (ref "TP4") (pin "1") (pinfunction "1_1") (pintype "passive"))
    )
    (net (code "8") (name "-6V_USH") (class "Default")
      (node (ref "C107") (pin "2") (pinfunction "2_2") (pintype "passive"))
      (node (ref "C115") (pin "1") (pinfunction "1_1") (pintype "passive"))
      (node (ref "C128") (pin "2") (pinfunction "2_2") (pintype "passive"))
      (node (ref "C139") (pin "2") (pinfunction "2_2") (pintype "passive"))
      (node (ref "D30") (pin "2") (pinfunction "A_2") (pintype "passive"))
      (node (ref "J19") (pin "1") (pintype "passive"))
      (node (ref "U19") (pin "5") (pinfunction "EN_5") (pintype "input"))
      (node (ref "U19") (pin "8") (pinfunction "VIN_8") (pintype "power_in"))
    )
    (net (code "9") (name "-6V_VSH") (class "Default")
      (node (ref "C108") (pin "2") (pinfunction "2_2") (pintype "passive"))
      (node (ref "C119") (pin "1") (pinfunction "1_1") (pintype "passive"))
      (node (ref "C130") (pin "2") (pinfunction "2_2") (pintype "passive"))
      (node (ref "C141") (pin "2") (pinfunction "2_2") (pintype "passive"))
      (node (ref "D33") (pin "2") (pinfunction "A_2") (pintype "passive"))
      (node (ref "J21") (pin "1") (pintype "passive"))
      (node (ref "U20") (pin "5") (pinfunction "EN_5") (pintype "input"))
      (node (ref "U20") (pin "8") (pinfunction "VIN_8") (pintype "power_in"))
    )
    (net (code "10") (name "DGND") (class "Default")
      (node (ref "C57") (pin "1") (pinfunction "1_1") (pintype "passive"))
      (node (ref "C58") (pin "1") (pinfunction "1_1") (pintype "passive"))
      (node (ref "C71") (pin "1") (pinfunction "1_1") (pintype "passive"))
      (node (ref "C72") (pin "1") (pinfunction "1_1") (pintype "passive"))
      (node (ref "C73") (pin "1") (pinfunction "1_1") (pintype "passive"))
      (node (ref "C74") (pin "1") (pinfunction "1_1") (pintype "passive"))
      (node (ref "C79") (pin "2") (pinfunction "-_2") (pintype "passive"))
      (node (ref "U12") (pin "4") (pinfunction "GND_4") (pintype "power_in"))
      (node (ref "U12") (pin "5") (pinfunction "GND_5") (pintype "power_in"))
      (node (ref "U13") (pin "4") (pinfunction "GND_4") (pintype "power_in"))
      (node (ref "U13") (pin "5") (pinfunction "GND_5") (pintype "power_in"))
    )
    (net (code "11") (name "GND_USH") (class "Default")
      (node (ref "C102") (pin "1") (pinfunction "1_1") (pintype "passive"))
      (node (ref "C107") (pin "1") (pinfunction "1_1") (pintype "passive"))
      (node (ref "C113") (pin "1") (pinfunction "1_1") (pintype "passive"))
      (node (ref "C114") (pin "2") (pinfunction "2_2") (pintype "passive"))
      (node (ref "C115") (pin "2") (pinfunction "2_2") (pintype "passive"))
      (node (ref "C116") (pin "1") (pinfunction "1_1") (pintype "passive"))
      (node (ref "C126") (pin "1") (pinfunction "1_1") (pintype "passive"))
      (node (ref "C127") (pin "2") (pinfunction "2_2") (pintype "passive"))
      (node (ref "C128") (pin "1") (pinfunction "1_1") (pintype "passive"))
      (node (ref "C138") (pin "2") (pinfunction "2_2") (pintype "passive"))
      (node (ref "C139") (pin "1") (pinfunction "1_1") (pintype "passive"))
      (node (ref "C57") (pin "2") (pinfunction "2_2") (pintype "passive"))
      (node (ref "C88") (pin "1") (pinfunction "1_1") (pintype "passive"))
      (node (ref "C89") (pin "2") (pinfunction "2_2") (pintype "passive"))
      (node (ref "C90") (pin "1") (pinfunction "1_1") (pintype "passive"))
      (node (ref "C96") (pin "2") (pinfunction "2_2") (pintype "passive"))
      (node (ref "D14") (pin "1") (pinfunction "C_1") (pintype "passive"))
      (node (ref "D19") (pin "1") (pinfunction "K_1") (pintype "passive"))
      (node (ref "D21") (pin "2") (pinfunction "A_2") (pintype "passive"))
      (node (ref "D4") (pin "2") (pinfunction "A_2") (pintype "passive"))
      (node (ref "J1") (pin "1") (pintype "passive"))
      (node (ref "J1") (pin "2") (pintype "passive"))
      (node (ref "J18") (pin "2") (pintype "passive"))
      (node (ref "J19") (pin "2") (pintype "passive"))
      (node (ref "R64") (pin "1") (pinfunction "1_1") (pintype "passive"))
      (node (ref "T1") (pin "4") (pinfunction "4_4") (pintype "passive"))
      (node (ref "U19") (pin "3") (pinfunction "NC_3") (pintype "passive"))
      (node (ref "U19") (pin "4") (pinfunction "GND_4") (pintype "power_in"))
      (node (ref "U19") (pin "9") (pinfunction "TPAD_9") (pintype "passive"))
      (node (ref "U21") (pin "1") (pinfunction "GND_1") (pintype "power_in"))
    )
    (net (code "12") (name "GND_VSH") (class "Default")
      (node (ref "C103") (pin "1") (pinfunction "1_1") (pintype "passive"))
      (node (ref "C108") (pin "1") (pinfunction "1_1") (pintype "passive"))
      (node (ref "C117") (pin "1") (pinfunction "1_1") (pintype "passive"))
      (node (ref "C118") (pin "2") (pinfunction "2_2") (pintype "passive"))
      (node (ref "C119") (pin "2") (pinfunction "2_2") (pintype "passive"))
      (node (ref "C120") (pin "1") (pinfunction "1_1") (pintype "passive"))
      (node (ref "C129") (pin "1") (pinfunction "1_1") (pintype "passive"))
      (node (ref "C130") (pin "1") (pinfunction "1_1") (pintype "passive"))
      (node (ref "C137") (pin "2") (pinfunction "2_2") (pintype "passive"))
      (node (ref "C140") (pin "2") (pinfunction "2_2") (pintype "passive"))
      (node (ref "C141") (pin "1") (pinfunction "1_1") (pintype "passive"))
      (node (ref "C58") (pin "2") (pinfunction "2_2") (pintype "passive"))
      (node (ref "C91") (pin "1") (pinfunction "1_1") (pintype "passive"))
      (node (ref "C92") (pin "1") (pinfunction "1_1") (pintype "passive"))
      (node (ref "C93") (pin "2") (pinfunction "2_2") (pintype "passive"))
      (node (ref "C98") (pin "2") (pinfunction "2_2") (pintype "passive"))
      (node (ref "D15") (pin "1") (pinfunction "C_1") (pintype "passive"))
      (node (ref "D20") (pin "1") (pinfunction "K_1") (pintype "passive"))
      (node (ref "D22") (pin "2") (pinfunction "A_2") (pintype "passive"))
      (node (ref "D5") (pin "2") (pinfunction "A_2") (pintype "passive"))
      (node (ref "J20") (pin "2") (pintype "passive"))
      (node (ref "J21") (pin "2") (pintype "passive"))
      (node (ref "J3") (pin "1") (pintype "passive"))
      (node (ref "J3") (pin "2") (pintype "passive"))
      (node (ref "R65") (pin "1") (pinfunction "1_1") (pintype "passive"))
      (node (ref "T2") (pin "4") (pinfunction "4_4") (pintype "passive"))
      (node (ref "U20") (pin "3") (pinfunction "NC_3") (pintype "passive"))
      (node (ref "U20") (pin "4") (pinfunction "GND_4") (pintype "power_in"))
      (node (ref "U20") (pin "9") (pinfunction "TPAD_9") (pintype "passive"))
      (node (ref "U22") (pin "1") (pinfunction "GND_1") (pintype "power_in"))
    )
    (net (code "13") (name "Net-(D4-C)") (class "Default")
      (node (ref "D4") (pin "1") (pinfunction "C_1") (pintype "passive"))
      (node (ref "R3") (pin "1") (pinfunction "1_1") (pintype "passive"))
    )
    (net (code "14") (name "Net-(D5-C)") (class "Default")
      (node (ref "D5") (pin "1") (pinfunction "C_1") (pintype "passive"))
      (node (ref "R4") (pin "1") (pinfunction "1_1") (pintype "passive"))
    )
    (net (code "15") (name "Net-(D14-A)") (class "Default")
      (node (ref "D14") (pin "2") (pinfunction "A_2") (pintype "passive"))
      (node (ref "R28") (pin "1") (pinfunction "1_1") (pintype "passive"))
    )
    (net (code "16") (name "Net-(D15-A)") (class "Default")
      (node (ref "D15") (pin "2") (pinfunction "A_2") (pintype "passive"))
      (node (ref "R30") (pin "1") (pinfunction "1_1") (pintype "passive"))
    )
    (net (code "17") (name "Net-(D29-A)") (class "Default")
      (node (ref "D29") (pin "2") (pinfunction "A_2") (pintype "passive"))
      (node (ref "D30") (pin "1") (pinfunction "K_1") (pintype "passive"))
      (node (ref "T1") (pin "6") (pinfunction "6_6") (pintype "passive"))
    )
    (net (code "18") (name "Net-(D32-A)") (class "Default")
      (node (ref "D32") (pin "2") (pinfunction "A_2") (pintype "passive"))
      (node (ref "D33") (pin "1") (pinfunction "K_1") (pintype "passive"))
      (node (ref "T2") (pin "6") (pinfunction "6_6") (pintype "passive"))
    )
    (net (code "19") (name "Net-(U12-D1)") (class "Default")
      (node (ref "T1") (pin "3") (pinfunction "3_3") (pintype "passive"))
      (node (ref "U12") (pin "1") (pinfunction "D1_1") (pintype "output"))
    )
    (net (code "20") (name "Net-(U12-D2)") (class "Default")
      (node (ref "T1") (pin "1") (pinfunction "1_1") (pintype "passive"))
      (node (ref "U12") (pin "3") (pinfunction "D2_3") (pintype "output"))
    )
    (net (code "21") (name "Net-(U13-D1)") (class "Default")
      (node (ref "T2") (pin "3") (pinfunction "3_3") (pintype "passive"))
      (node (ref "U13") (pin "1") (pinfunction "D1_1") (pintype "output"))
    )
    (net (code "22") (name "Net-(U13-D2)") (class "Default")
      (node (ref "T2") (pin "1") (pinfunction "1_1") (pintype "passive"))
      (node (ref "U13") (pin "3") (pinfunction "D2_3") (pintype "output"))
    )
    (net (code "23") (name "Net-(U19-FB)") (class "Default")
      (node (ref "C97") (pin "1") (pinfunction "1_1") (pintype "passive"))
      (node (ref "R61") (pin "1") (pinfunction "1_1") (pintype "passive"))
      (node (ref "R64") (pin "2") (pinfunction "2_2") (pintype "passive"))
      (node (ref "U19") (pin "2") (pinfunction "FB_2") (pintype "input"))
    )
    (net (code "24") (name "Net-(U19-NR{slash}SS)") (class "Default")
      (node (ref "C116") (pin "2") (pinfunction "2_2") (pintype "passive"))
      (node (ref "U19") (pin "6") (pinfunction "NR/SS_6") (pintype "input"))
    )
    (net (code "25") (name "Net-(U19-OUT)") (class "Default")
      (node (ref "C88") (pin "2") (pinfunction "2_2") (pintype "passive"))
      (node (ref "C97") (pin "2") (pinfunction "2_2") (pintype "passive"))
      (node (ref "FB9") (pin "1") (pinfunction "1_1") (pintype "passive"))
      (node (ref "R61") (pin "2") (pinfunction "2_2") (pintype "passive"))
      (node (ref "U19") (pin "1") (pinfunction "OUT_1") (pintype "power_in"))
    )
    (net (code "26") (name "Net-(U20-FB)") (class "Default")
      (node (ref "C99") (pin "1") (pinfunction "1_1") (pintype "passive"))
      (node (ref "R62") (pin "1") (pinfunction "1_1") (pintype "passive"))
      (node (ref "R65") (pin "2") (pinfunction "2_2") (pintype "passive"))
      (node (ref "U20") (pin "2") (pinfunction "FB_2") (pintype "input"))
    )
    (net (code "27") (name "Net-(U20-NR{slash}SS)") (class "Default")
      (node (ref "C120") (pin "2") (pinfunction "2_2") (pintype "passive"))
      (node (ref "U20") (pin "6") (pinfunction "NR/SS_6") (pintype "input"))
    )
    (net (code "28") (name "Net-(U20-OUT)") (class "Default")
      (node (ref "C91") (pin "2") (pinfunction "2_2") (pintype "passive"))
      (node (ref "C99") (pin "2") (pinfunction "2_2") (pintype "passive"))
      (node (ref "FB10") (pin "1") (pinfunction "1_1") (pintype "passive"))
      (node (ref "R62") (pin "2") (pinfunction "2_2") (pintype "passive"))
      (node (ref "U20") (pin "1") (pinfunction "OUT_1") (pintype "power_in"))
    )
    (net (code "29") (name "Net-(U21-OUT)") (class "Default")
      (node (ref "C113") (pin "2") (pinfunction "2_2") (pintype "passive"))
      (node (ref "FB12") (pin "1") (pinfunction "1_1") (pintype "passive"))
      (node (ref "U21") (pin "3") (pinfunction "OUT_3") (pintype "output"))
    )
    (net (code "30") (name "Net-(U22-OUT)") (class "Default")
      (node (ref "C117") (pin "2") (pinfunction "2_2") (pintype "passive"))
      (node (ref "FB13") (pin "1") (pinfunction "1_1") (pintype "passive"))
      (node (ref "U22") (pin "3") (pinfunction "OUT_3") (pintype "output"))
    )
    (net (code "31") (name "unconnected-(T1-Pad5)") (class "Default")
      (node (ref "T1") (pin "5") (pinfunction "5_5") (pintype "passive"))
    )
    (net (code "32") (name "unconnected-(T2-Pad5)") (class "Default")
      (node (ref "T2") (pin "5") (pinfunction "5_5") (pintype "passive"))
    )
    (net (code "33") (name "unconnected-(U19-DNC-Pad7)") (class "Default")
      (node (ref "U19") (pin "7") (pinfunction "DNC_7") (pintype "passive"))
    )
    (net (code "34") (name "unconnected-(U20-DNC-Pad7)") (class "Default")
      (node (ref "U20") (pin "7") (pinfunction "DNC_7") (pintype "passive"))
    )
    (net (code "35") (name "unconnected-(U21-NC-Pad4)") (class "Default")
      (node (ref "U21") (pin "4") (pinfunction "NC_4") (pintype "power_in"))
    )
    (net (code "36") (name "unconnected-(U21-NC-Pad5)") (class "Default")
      (node (ref "U21") (pin "5") (pinfunction "NC_5") (pintype "power_in"))
    )
    (net (code "37") (name "unconnected-(U22-NC-Pad4)") (class "Default")
      (node (ref "U22") (pin "4") (pinfunction "NC_4") (pintype "power_in"))
    )
    (net (code "38") (name "unconnected-(U22-NC-Pad5)") (class "Default")
      (node (ref "U22") (pin "5") (pinfunction "NC_5") (pintype "power_in"))
    )
  )
)
